# rgb_led.net
KiCad netlist of a schematic drawn in EAGLE
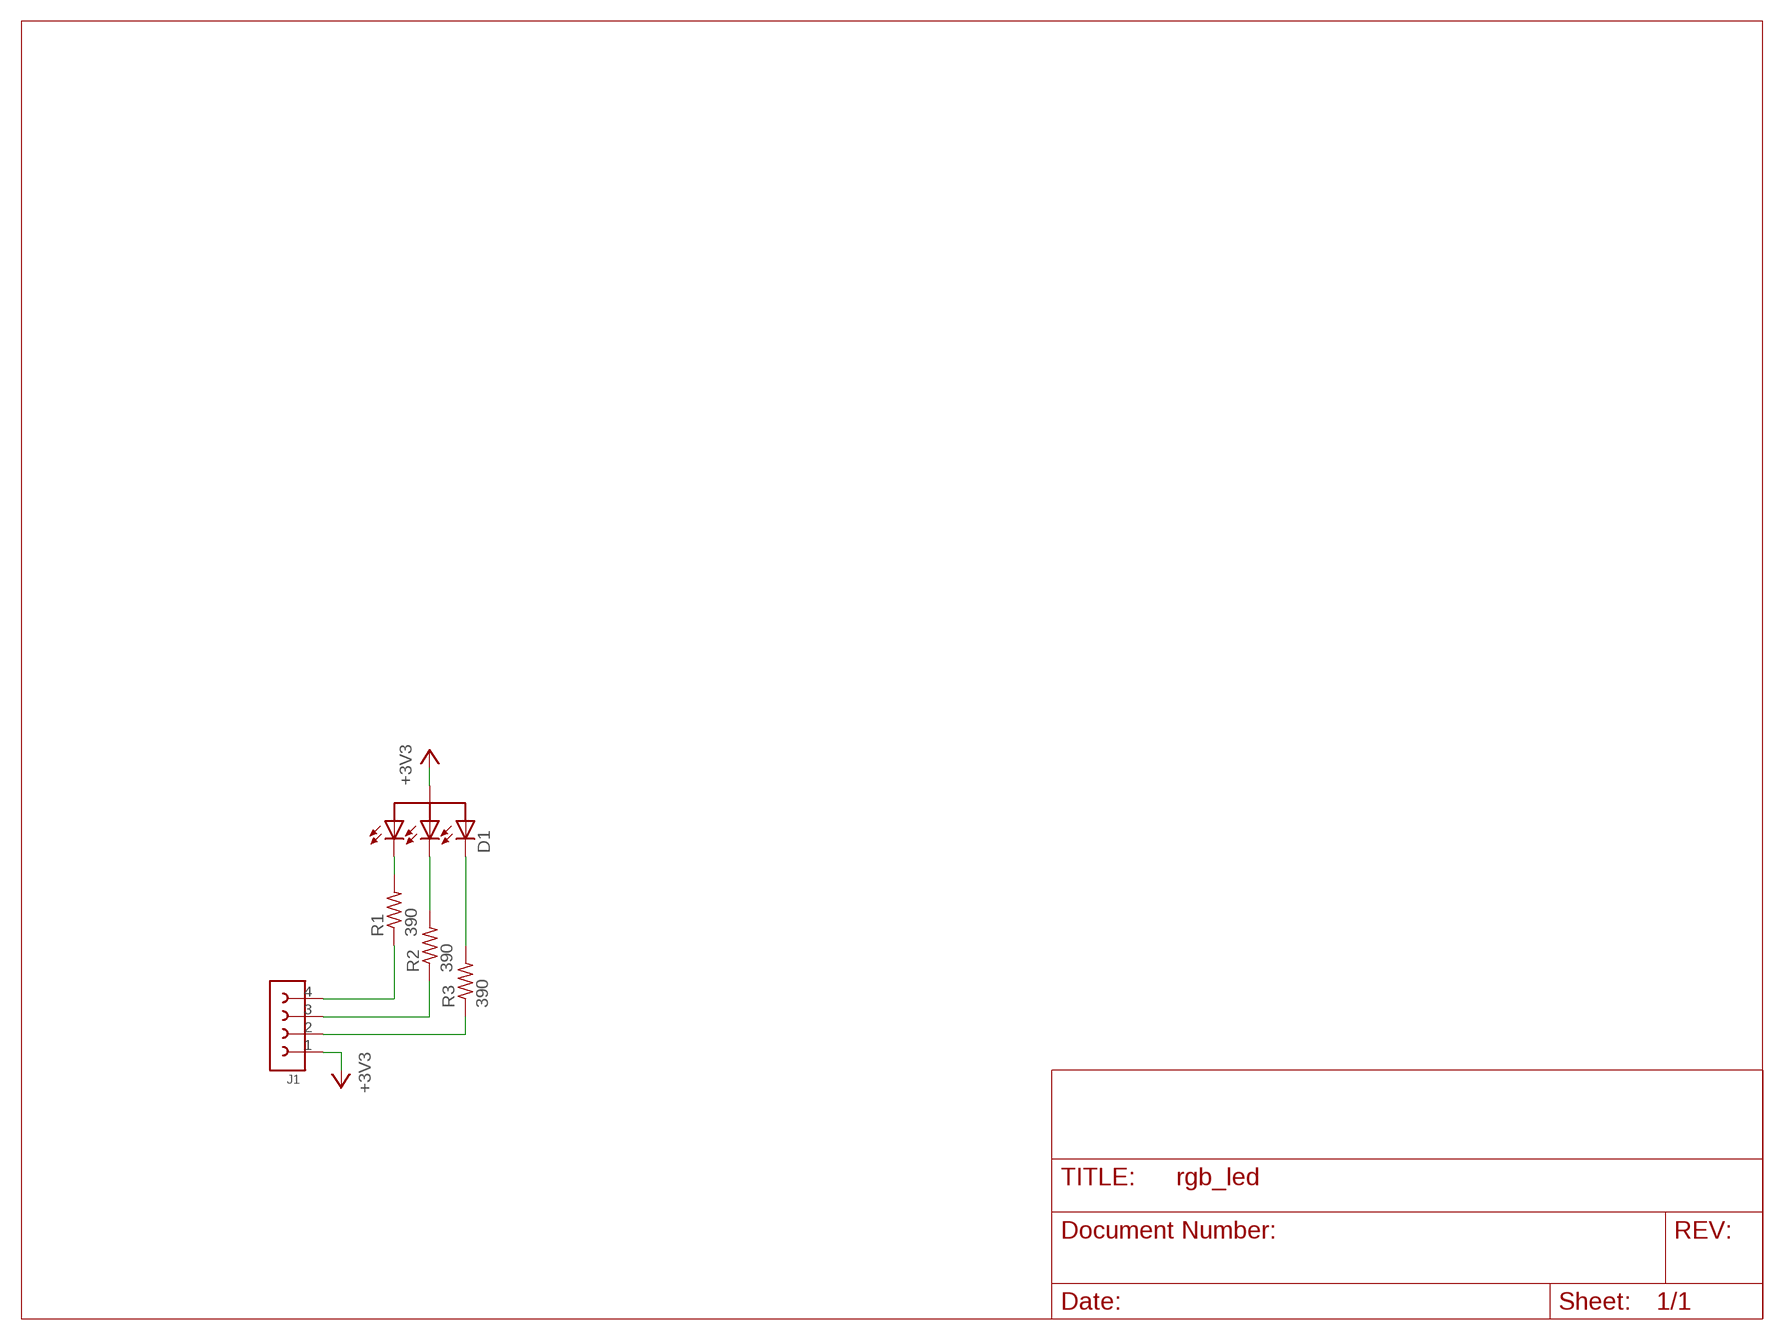
[diagram p0: schematic, sheet 1]

(export (version "E")
  (design (tool "Eeschema 10.0.6"))
  (components
    (comp (ref "D1")
      (value "SM1210RGB")
      (footprint "eagle-import:D1210")
      (libsource (lib "eagle-import") (part "SM1210RGB"))
    )
    (comp (ref "J1")
      (value "61300411121")
      (footprint "eagle-import:PHSP254P1016X254X1154-4S")
      (libsource (lib "eagle-import") (part "6130041?1121"))
    )
    (comp (ref "R1")
      (value "390")
      (footprint "eagle-import:RESC0603")
      (libsource (lib "eagle-import") (part "CRG?0603F390R"))
    )
    (comp (ref "R2")
      (value "390")
      (footprint "eagle-import:RESC0603")
      (libsource (lib "eagle-import") (part "CRG?0603F390R"))
    )
    (comp (ref "R3")
      (value "390")
      (footprint "eagle-import:RESC0603")
      (libsource (lib "eagle-import") (part "CRG?0603F390R"))
    )
  )
  (nets
    (net (code "1") (name "+3V3") (class "Default")
      (node (ref "D1") (pin "1") (pinfunction "A_1") (pintype "passive"))
      (node (ref "J1") (pin "1") (pinfunction "1_1") (pintype "passive"))
    )
    (net (code "2") (name "Net-(D1-C1)") (class "Default")
      (node (ref "D1") (pin "3") (pinfunction "C1_3") (pintype "passive"))
      (node (ref "R3") (pin "P$2") (pinfunction "2_P$2") (pintype "passive"))
    )
    (net (code "3") (name "Net-(D1-C2)") (class "Default")
      (node (ref "D1") (pin "4") (pinfunction "C2_4") (pintype "passive"))
      (node (ref "R2") (pin "P$2") (pinfunction "2_P$2") (pintype "passive"))
    )
    (net (code "4") (name "Net-(D1-C3)") (class "Default")
      (node (ref "D1") (pin "2") (pinfunction "C3_2") (pintype "passive"))
      (node (ref "R1") (pin "P$2") (pinfunction "2_P$2") (pintype "passive"))
    )
    (net (code "5") (name "Net-(R1-1)") (class "Default")
      (node (ref "J1") (pin "4") (pinfunction "4_4") (pintype "passive"))
      (node (ref "R1") (pin "P$1") (pinfunction "1_P$1") (pintype "passive"))
    )
    (net (code "6") (name "Net-(R2-1)") (class "Default")
      (node (ref "J1") (pin "3") (pinfunction "3_3") (pintype "passive"))
      (node (ref "R2") (pin "P$1") (pinfunction "1_P$1") (pintype "passive"))
    )
    (net (code "7") (name "Net-(R3-1)") (class "Default")
      (node (ref "J1") (pin "2") (pinfunction "2_2") (pintype "passive"))
      (node (ref "R3") (pin "P$1") (pinfunction "1_P$1") (pintype "passive"))
    )
  )
)
